# transmitter.net
KiCad netlist of a schematic drawn in EAGLE
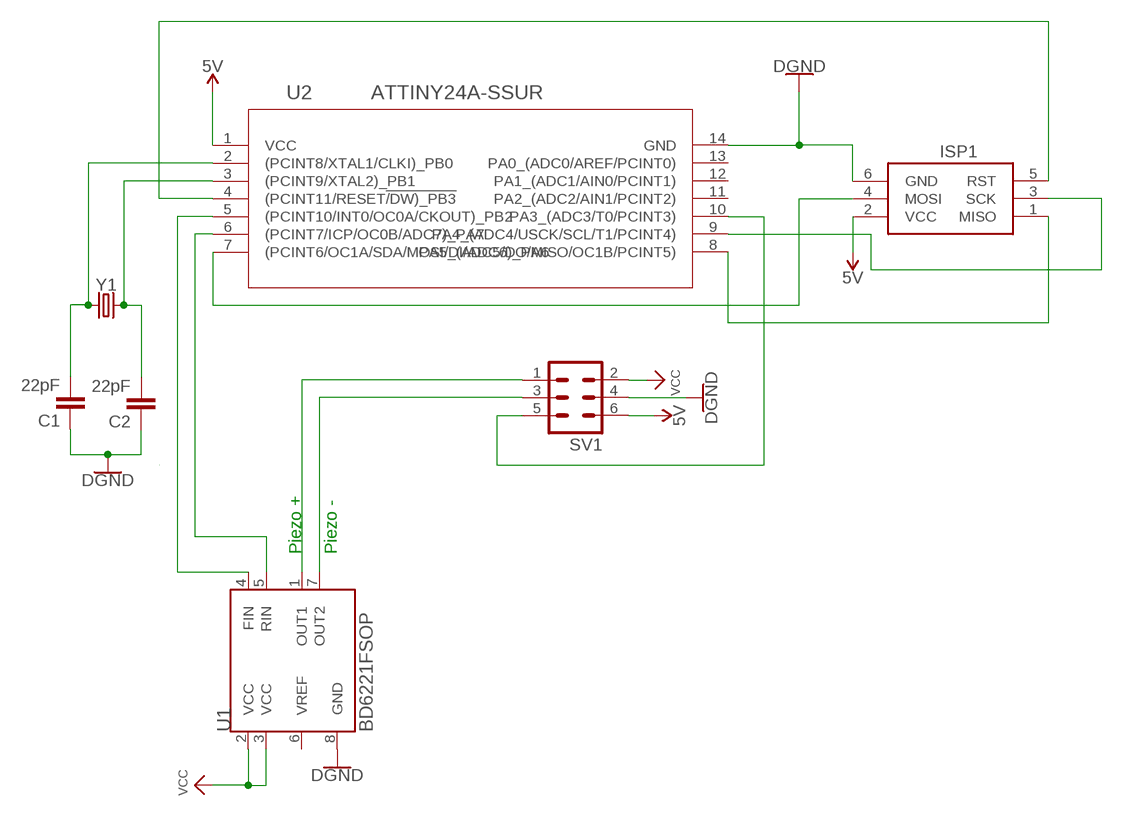
[diagram p0: schematic, sheet 1]

(export (version "E")
  (design (tool "Eeschema 10.0.6"))
  (components
    (comp (ref "C1")
      (value "22pF")
      (footprint "eagle-import:0603")
      (libsource (lib "eagle-import") (part "0.75PF-50V(-/+.25PF)(0603)"))
    )
    (comp (ref "C2")
      (value "22pF")
      (footprint "eagle-import:0603")
      (libsource (lib "eagle-import") (part "0.75PF-50V(-/+.25PF)(0603)"))
    )
    (comp (ref "ISP1")
      (value "AVRISP-6")
      (footprint "eagle-import:AVRISP")
      (libsource (lib "eagle-import") (part "AVRISP-6"))
    )
    (comp (ref "SV1")
      (value "MA03-2")
      (footprint "eagle-import:MA03-2")
      (libsource (lib "eagle-import") (part "MA03-2"))
    )
    (comp (ref "U1")
      (value "BD6221FSOP")
      (footprint "eagle-import:SOP8")
      (libsource (lib "eagle-import") (part "BD6221FSOP"))
    )
    (comp (ref "U2")
      (value "ATTINY24A-SSUR")
      (footprint "eagle-import:14S1")
      (fields (field (name "MANUFACTURER_PART_NUMBER") "ATTINY24ASSUR"))
      (libsource (lib "eagle-import") (part "ATTINY24A-SSUR"))
    )
    (comp (ref "Y1")
      (value "CRYSTALPTH-HC49US")
      (footprint "eagle-import:HC49US")
      (libsource (lib "eagle-import") (part "CRYSTALPTH-HC49US"))
    )
  )
  (nets
    (net (code "1") (name "5V") (class "Default")
      (node (ref "ISP1") (pin "2") (pinfunction "VCC_2") (pintype "power_in"))
      (node (ref "SV1") (pin "6") (pinfunction "6_6") (pintype "passive"))
      (node (ref "U2") (pin "1") (pinfunction "VCC_1") (pintype "power_in"))
    )
    (net (code "2") (name "DGND") (class "Default")
      (node (ref "C1") (pin "1") (pinfunction "1_1") (pintype "passive"))
      (node (ref "C2") (pin "1") (pinfunction "1_1") (pintype "passive"))
      (node (ref "ISP1") (pin "6") (pinfunction "GND_6") (pintype "power_in"))
      (node (ref "SV1") (pin "4") (pinfunction "4_4") (pintype "passive"))
      (node (ref "U1") (pin "8") (pinfunction "GND_8") (pintype "power_in"))
      (node (ref "U2") (pin "14") (pinfunction "GND_14") (pintype "power_in"))
    )
    (net (code "3") (name "Net-(ISP1-MISO)") (class "Default")
      (node (ref "ISP1") (pin "1") (pinfunction "MISO_1") (pintype "input"))
      (node (ref "U2") (pin "8") (pinfunction "PA5_(ADC5/DO/MISO/OC1B/PCINT5)_8") (pintype "bidirectional"))
    )
    (net (code "4") (name "Net-(ISP1-MOSI)") (class "Default")
      (node (ref "ISP1") (pin "4") (pinfunction "MOSI_4") (pintype "output"))
      (node (ref "U2") (pin "7") (pinfunction "(PCINT6/OC1A/SDA/MOSI/DI/ADC6)_PA6_7") (pintype "bidirectional"))
    )
    (net (code "5") (name "Net-(ISP1-RST)") (class "Default")
      (node (ref "ISP1") (pin "5") (pinfunction "RST_5") (pintype "output"))
      (node (ref "U2") (pin "4") (pinfunction "(PCINT11/RESET~{/DW})_PB3_4") (pintype "bidirectional"))
    )
    (net (code "6") (name "Net-(ISP1-SCK)") (class "Default")
      (node (ref "ISP1") (pin "3") (pinfunction "SCK_3") (pintype "output"))
      (node (ref "U2") (pin "9") (pinfunction "PA4_(ADC4/USCK/SCL/T1/PCINT4)_9") (pintype "bidirectional"))
    )
    (net (code "7") (name "Net-(U1-FIN)") (class "Default")
      (node (ref "U1") (pin "4") (pinfunction "FIN_4") (pintype "input"))
      (node (ref "U2") (pin "5") (pinfunction "(PCINT10/INT0/OC0A/CKOUT)_PB2_5") (pintype "bidirectional"))
    )
    (net (code "8") (name "Net-(U1-OUT1)") (class "Default")
      (node (ref "SV1") (pin "1") (pinfunction "1_1") (pintype "passive"))
      (node (ref "U1") (pin "1") (pinfunction "OUT1_1") (pintype "output"))
    )
    (net (code "9") (name "Net-(U1-OUT2)") (class "Default")
      (node (ref "SV1") (pin "3") (pinfunction "3_3") (pintype "passive"))
      (node (ref "U1") (pin "7") (pinfunction "OUT2_7") (pintype "output"))
    )
    (net (code "10") (name "Net-(U1-RIN)") (class "Default")
      (node (ref "U1") (pin "5") (pinfunction "RIN_5") (pintype "input"))
      (node (ref "U2") (pin "6") (pinfunction "(PCINT7/ICP/OC0B/ADC7)_PA7_6") (pintype "bidirectional"))
    )
    (net (code "11") (name "Net-(U2-(PCINT8{slash}XTAL1{slash}CLKI)_PB0)") (class "Default")
      (node (ref "C1") (pin "2") (pinfunction "2_2") (pintype "passive"))
      (node (ref "U2") (pin "2") (pinfunction "(PCINT8/XTAL1/CLKI)_PB0_2") (pintype "bidirectional"))
      (node (ref "Y1") (pin "1") (pinfunction "1_1") (pintype "passive"))
    )
    (net (code "12") (name "Net-(U2-(PCINT9{slash}XTAL2)_PB1)") (class "Default")
      (node (ref "C2") (pin "2") (pinfunction "2_2") (pintype "passive"))
      (node (ref "U2") (pin "3") (pinfunction "(PCINT9/XTAL2)_PB1_3") (pintype "bidirectional"))
      (node (ref "Y1") (pin "2") (pinfunction "2_2") (pintype "passive"))
    )
    (net (code "13") (name "Net-(U2-PA3_(ADC3{slash}T0{slash}PCINT3))") (class "Default")
      (node (ref "SV1") (pin "5") (pinfunction "5_5") (pintype "passive"))
      (node (ref "U2") (pin "10") (pinfunction "PA3_(ADC3/T0/PCINT3)_10") (pintype "bidirectional"))
    )
    (net (code "14") (name "VCC") (class "Default")
      (node (ref "SV1") (pin "2") (pinfunction "2_2") (pintype "passive"))
      (node (ref "U1") (pin "2") (pinfunction "VCC_2") (pintype "power_in"))
      (node (ref "U1") (pin "3") (pinfunction "VCC_3") (pintype "power_in"))
    )
    (net (code "15") (name "unconnected-(U1-VREF-Pad6)") (class "Default")
      (node (ref "U1") (pin "6") (pinfunction "VREF_6") (pintype "bidirectional"))
    )
    (net (code "16") (name "unconnected-(U2-PA0_(ADC0{slash}AREF{slash}PCINT0)-Pad13)") (class "Default")
      (node (ref "U2") (pin "13") (pinfunction "PA0_(ADC0/AREF/PCINT0)_13") (pintype "bidirectional"))
    )
    (net (code "17") (name "unconnected-(U2-PA1_(ADC1{slash}AIN0{slash}PCINT1)-Pad12)") (class "Default")
      (node (ref "U2") (pin "12") (pinfunction "PA1_(ADC1/AIN0/PCINT1)_12") (pintype "bidirectional"))
    )
    (net (code "18") (name "unconnected-(U2-PA2_(ADC2{slash}AIN1{slash}PCINT2)-Pad11)") (class "Default")
      (node (ref "U2") (pin "11") (pinfunction "PA2_(ADC2/AIN1/PCINT2)_11") (pintype "bidirectional"))
    )
  )
)
